# HDMI.net
KiCad netlist of a schematic drawn in Altium Designer
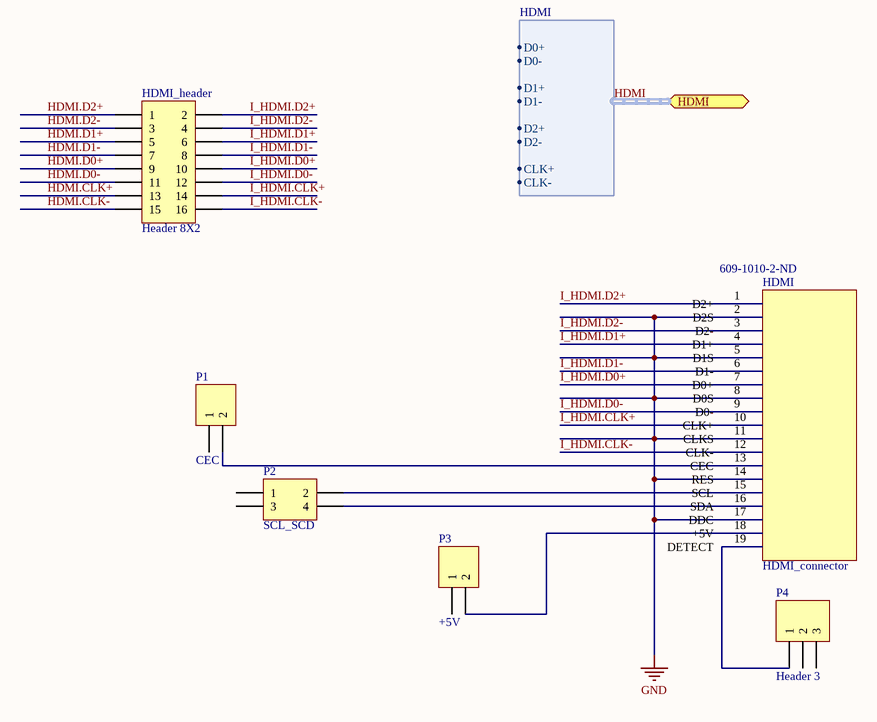
[diagram p0: HDMI.SchDoc]

(export (version "E")
  (design (tool "Eeschema 10.0.6"))
  (components
    (comp (ref "HDMI")
      (value "HDMI_connector")
      (footprint "HDMI-type-A")
      (fields
        (field (name "SUPPLIER PART NUMBER 1") "609-1010-2-ND")
        (field (name "MANUFACTURER") "FCI")
        (field (name "MANUFACTURER PART NUMBER") "10029449-001RLF")
      )
      (libsource (lib "HDMI") (part "HDMI_connector"))
    )
    (comp (ref "HDMI_header")
      (value "Header 8X2")
      (footprint "HDR2X8")
      (description "Header, 8-Pin, Dual row")
      (fields (field (name "PUBLISHER") "Altium Limited"))
      (libsource (lib "Miscellaneous Connectors") (part "Header 8X2"))
    )
    (comp (ref "P1")
      (value "CEC")
      (footprint "HDR1X2")
      (description "Header, 2-Pin")
      (fields (field (name "PUBLISHER") "Altium Limited"))
      (libsource (lib "Miscellaneous Connectors") (part "Header 2"))
    )
    (comp (ref "P2")
      (value "SCL_SCD")
      (footprint "HDR2X2")
      (description "Header, 2-Pin, Dual row")
      (fields (field (name "PUBLISHER") "Altium Limited"))
      (libsource (lib "Miscellaneous Connectors") (part "Header 2X2"))
    )
    (comp (ref "P3")
      (value "+5V")
      (footprint "HDR1X2")
      (description "Header, 2-Pin")
      (fields (field (name "PUBLISHER") "Altium Limited"))
      (libsource (lib "Miscellaneous Connectors") (part "Header 2"))
    )
    (comp (ref "P4")
      (value "Header 3")
      (footprint "HDR1X3")
      (description "Header, 3-Pin")
      (fields (field (name "PUBLISHER") "Altium Limited"))
      (libsource (lib "Miscellaneous Connectors") (part "Header 3"))
    )
  )
  (nets
    (net (code "2") (name "/HDMI.CLK+") (class "Default")
      (node (ref "HDMI_header") (pin "13") (pinfunction "13_13") (pintype "passive"))
    )
    (net (code "3") (name "/HDMI.CLK-") (class "Default")
      (node (ref "HDMI_header") (pin "15") (pinfunction "15_15") (pintype "passive"))
    )
    (net (code "4") (name "/HDMI.D0+") (class "Default")
      (node (ref "HDMI_header") (pin "9") (pinfunction "9_9") (pintype "passive"))
    )
    (net (code "5") (name "/HDMI.D0-") (class "Default")
      (node (ref "HDMI_header") (pin "11") (pinfunction "11_11") (pintype "passive"))
    )
    (net (code "6") (name "/HDMI.D1+") (class "Default")
      (node (ref "HDMI_header") (pin "5") (pinfunction "5_5") (pintype "passive"))
    )
    (net (code "7") (name "/HDMI.D1-") (class "Default")
      (node (ref "HDMI_header") (pin "7") (pinfunction "7_7") (pintype "passive"))
    )
    (net (code "8") (name "/HDMI.D2+") (class "Default")
      (node (ref "HDMI_header") (pin "1") (pinfunction "1_1") (pintype "passive"))
    )
    (net (code "9") (name "/HDMI.D2-") (class "Default")
      (node (ref "HDMI_header") (pin "3") (pinfunction "3_3") (pintype "passive"))
    )
    (net (code "11") (name "/I_HDMI.CLK+") (class "Default")
      (node (ref "HDMI") (pin "10") (pinfunction "CLK+_10") (pintype "passive"))
      (node (ref "HDMI_header") (pin "14") (pinfunction "14_14") (pintype "passive"))
    )
    (net (code "12") (name "/I_HDMI.CLK-") (class "Default")
      (node (ref "HDMI") (pin "12") (pinfunction "CLK-_12") (pintype "passive"))
      (node (ref "HDMI_header") (pin "16") (pinfunction "16_16") (pintype "passive"))
    )
    (net (code "13") (name "/I_HDMI.D0+") (class "Default")
      (node (ref "HDMI") (pin "7") (pinfunction "D0+_7") (pintype "passive"))
      (node (ref "HDMI_header") (pin "10") (pinfunction "10_10") (pintype "passive"))
    )
    (net (code "14") (name "/I_HDMI.D0-") (class "Default")
      (node (ref "HDMI") (pin "9") (pinfunction "D0-_9") (pintype "passive"))
      (node (ref "HDMI_header") (pin "12") (pinfunction "12_12") (pintype "passive"))
    )
    (net (code "15") (name "/I_HDMI.D1+") (class "Default")
      (node (ref "HDMI") (pin "4") (pinfunction "D1+_4") (pintype "passive"))
      (node (ref "HDMI_header") (pin "6") (pinfunction "6_6") (pintype "passive"))
    )
    (net (code "16") (name "/I_HDMI.D1-") (class "Default")
      (node (ref "HDMI") (pin "6") (pinfunction "D1-_6") (pintype "passive"))
      (node (ref "HDMI_header") (pin "8") (pinfunction "8_8") (pintype "passive"))
    )
    (net (code "17") (name "/I_HDMI.D2+") (class "Default")
      (node (ref "HDMI") (pin "1") (pinfunction "D2+_1") (pintype "passive"))
      (node (ref "HDMI_header") (pin "2") (pinfunction "2_2") (pintype "passive"))
    )
    (net (code "18") (name "/I_HDMI.D2-") (class "Default")
      (node (ref "HDMI") (pin "3") (pinfunction "D2-_3") (pintype "passive"))
      (node (ref "HDMI_header") (pin "4") (pinfunction "4_4") (pintype "passive"))
    )
    (net (code "19") (name "GND") (class "Default")
      (node (ref "HDMI") (pin "11") (pinfunction "CLKS_11") (pintype "passive"))
      (node (ref "HDMI") (pin "14") (pinfunction "RES_14") (pintype "passive"))
      (node (ref "HDMI") (pin "17") (pinfunction "DDC_17") (pintype "passive"))
      (node (ref "HDMI") (pin "2") (pinfunction "D2S_2") (pintype "passive"))
      (node (ref "HDMI") (pin "5") (pinfunction "D1S_5") (pintype "passive"))
      (node (ref "HDMI") (pin "8") (pinfunction "D0S_8") (pintype "passive"))
    )
    (net (code "20") (name "Net-(HDMI-+5V)") (class "Default")
      (node (ref "HDMI") (pin "18") (pinfunction "+5V_18") (pintype "passive"))
      (node (ref "P3") (pin "2") (pinfunction "2_2") (pintype "passive"))
    )
    (net (code "21") (name "Net-(HDMI-CEC)") (class "Default")
      (node (ref "HDMI") (pin "13") (pinfunction "CEC_13") (pintype "passive"))
      (node (ref "P1") (pin "2") (pinfunction "2_2") (pintype "passive"))
    )
    (net (code "22") (name "Net-(HDMI-DETECT)") (class "Default")
      (node (ref "HDMI") (pin "19") (pinfunction "DETECT_19") (pintype "passive"))
      (node (ref "P4") (pin "1") (pinfunction "1_1") (pintype "passive"))
    )
    (net (code "23") (name "Net-(HDMI-SCL)") (class "Default")
      (node (ref "HDMI") (pin "15") (pinfunction "SCL_15") (pintype "passive"))
      (node (ref "P2") (pin "2") (pinfunction "2_2") (pintype "passive"))
    )
    (net (code "24") (name "Net-(HDMI-SDA)") (class "Default")
      (node (ref "HDMI") (pin "16") (pinfunction "SDA_16") (pintype "passive"))
      (node (ref "P2") (pin "4") (pinfunction "4_4") (pintype "passive"))
    )
    (net (code "25") (name "unconnected-(P1-Pad1)") (class "Default")
      (node (ref "P1") (pin "1") (pinfunction "1_1") (pintype "passive"))
    )
    (net (code "26") (name "unconnected-(P2-Pad1)") (class "Default")
      (node (ref "P2") (pin "1") (pinfunction "1_1") (pintype "passive"))
    )
    (net (code "27") (name "unconnected-(P2-Pad3)") (class "Default")
      (node (ref "P2") (pin "3") (pinfunction "3_3") (pintype "passive"))
    )
    (net (code "28") (name "unconnected-(P3-Pad1)") (class "Default")
      (node (ref "P3") (pin "1") (pinfunction "1_1") (pintype "passive"))
    )
    (net (code "29") (name "unconnected-(P4-Pad2)") (class "Default")
      (node (ref "P4") (pin "2") (pinfunction "2_2") (pintype "passive"))
    )
    (net (code "30") (name "unconnected-(P4-Pad3)") (class "Default")
      (node (ref "P4") (pin "3") (pinfunction "3_3") (pintype "passive"))
    )
  )
)
